# FlipDot_Matrix.net
KiCad netlist of a schematic drawn in Altium Designer
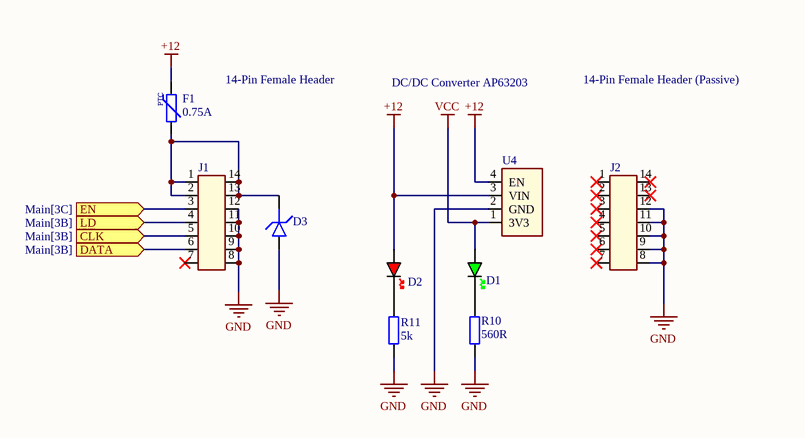
[diagram p0: FlipDot_Matrix.SchDoc]

(export (version "E")
  (design (tool "Eeschema 10.0.6"))
  (components
    (comp (ref "D1")
      (value "GREEN")
      (footprint "LED_0603_GREEN")
      (description "LED 0603 GREEN SMD")
      (libsource (lib "Schematic-Lib-PhilsLab") (part "LED_0603_GREEN"))
    )
    (comp (ref "D2")
      (value "RED")
      (footprint "LED_0603_RED")
      (description "LED 0603 RED SMD")
      (libsource (lib "Schematic-Lib-PhilsLab") (part "LED_0603_RED"))
    )
    (comp (ref "D3")
      (value "D_TVS_0402")
      (footprint "D_0402")
      (description "Diode TVS / ESD 0402")
      (libsource (lib "Schematic-Lib-PhilsLab") (part "D_TVS_0402"))
    )
    (comp (ref "F1")
      (value "0.75A")
      (footprint "FUSE_1206")
      (description "Fuse PPTC SMD 1206")
      (libsource (lib "Schematic-Lib-PhilsLab") (part "FUSE_PPTC_1206"))
    )
    (comp (ref "J1")
      (value "14-Pin Female Header")
      (footprint "PCB_Library_TM:SAMTEC_14_PIN")
      (libsource (lib "Schematic_Library_TM") (part "14-Pin-Connector"))
    )
    (comp (ref "J2")
      (value "14-Pin Female Header (Passive)")
      (footprint "PCB_Library_TM:SAMTEC_14_PIN")
      (libsource (lib "") (part "14-Pin-Connector_1"))
    )
    (comp (ref "R10")
      (value "560R")
      (footprint "RES_0805")
      (description "Resistor SMD 0805")
      (libsource (lib "Schematic-Lib-PhilsLab") (part "RES_0805"))
    )
    (comp (ref "R11")
      (value "5k")
      (footprint "RES_0805")
      (description "Resistor SMD 0805")
      (libsource (lib "Schematic-Lib-PhilsLab") (part "RES_0805"))
    )
    (comp (ref "U4")
      (value "DC/DC Converter AP63203")
      (footprint "DC/DC_CONVERTER")
      (libsource (lib "Schematic_Library_TM") (part "DC/DC Converter AP63203"))
    )
  )
  (nets
    (net (code "1") (name "+12") (class "Default")
      (node (ref "D2") (pin "A") (pinfunction "A_A") (pintype "passive"))
      (node (ref "F1") (pin "2") (pinfunction "2_2") (pintype "passive"))
      (node (ref "U4") (pin "3") (pinfunction "VIN_3") (pintype "power_in"))
      (node (ref "U4") (pin "4") (pinfunction "EN_4") (pintype "power_in"))
    )
    (net (code "2") (name "/CLK") (class "Default")
      (node (ref "J1") (pin "5") (pinfunction "5_5") (pintype "passive"))
    )
    (net (code "3") (name "/DATA") (class "Default")
      (node (ref "J1") (pin "6") (pinfunction "6_6") (pintype "passive"))
    )
    (net (code "4") (name "/EN") (class "Default")
      (node (ref "J1") (pin "3") (pinfunction "3_3") (pintype "passive"))
    )
    (net (code "5") (name "/LD") (class "Default")
      (node (ref "J1") (pin "4") (pinfunction "4_4") (pintype "passive"))
    )
    (net (code "6") (name "GND") (class "Default")
      (node (ref "D3") (pin "A") (pinfunction "A_A") (pintype "passive"))
      (node (ref "J1") (pin "10") (pinfunction "10_10") (pintype "passive"))
      (node (ref "J1") (pin "11") (pinfunction "11_11") (pintype "passive"))
      (node (ref "J1") (pin "12") (pinfunction "12_12") (pintype "passive"))
      (node (ref "J1") (pin "8") (pinfunction "8_8") (pintype "passive"))
      (node (ref "J1") (pin "9") (pinfunction "9_9") (pintype "passive"))
      (node (ref "J2") (pin "10") (pinfunction "10_10") (pintype "passive"))
      (node (ref "J2") (pin "11") (pinfunction "11_11") (pintype "passive"))
      (node (ref "J2") (pin "12") (pinfunction "12_12") (pintype "passive"))
      (node (ref "J2") (pin "8") (pinfunction "8_8") (pintype "passive"))
      (node (ref "J2") (pin "9") (pinfunction "9_9") (pintype "passive"))
      (node (ref "R10") (pin "1") (pinfunction "1_1") (pintype "passive"))
      (node (ref "R11") (pin "1") (pinfunction "1_1") (pintype "passive"))
      (node (ref "U4") (pin "2") (pinfunction "GND_2") (pintype "power_in"))
    )
    (net (code "7") (name "Net-(D1-PadK)") (class "Default")
      (node (ref "D1") (pin "K") (pinfunction "K_K") (pintype "passive"))
      (node (ref "R10") (pin "2") (pinfunction "2_2") (pintype "passive"))
    )
    (net (code "8") (name "Net-(D2-PadK)") (class "Default")
      (node (ref "D2") (pin "K") (pinfunction "K_K") (pintype "passive"))
      (node (ref "R11") (pin "2") (pinfunction "2_2") (pintype "passive"))
    )
    (net (code "9") (name "Net-(D3-PadK)") (class "Default")
      (node (ref "D3") (pin "K") (pinfunction "K_K") (pintype "passive"))
      (node (ref "F1") (pin "1") (pinfunction "1_1") (pintype "passive"))
      (node (ref "J1") (pin "1") (pinfunction "1_1") (pintype "passive"))
      (node (ref "J1") (pin "13") (pinfunction "13_13") (pintype "passive"))
      (node (ref "J1") (pin "14") (pinfunction "14_14") (pintype "passive"))
      (node (ref "J1") (pin "2") (pinfunction "2_2") (pintype "passive"))
    )
    (net (code "10") (name "VCC") (class "Default")
      (node (ref "D1") (pin "A") (pinfunction "A_A") (pintype "passive"))
      (node (ref "U4") (pin "1") (pinfunction "3V3_1") (pintype "power_in"))
    )
    (net (code "11") (name "unconnected-(J1-Pad7)") (class "Default")
      (node (ref "J1") (pin "7") (pinfunction "7_7") (pintype "passive+no_connect"))
    )
    (net (code "12") (name "unconnected-(J2-Pad1)") (class "Default")
      (node (ref "J2") (pin "1") (pinfunction "1_1") (pintype "passive+no_connect"))
    )
    (net (code "13") (name "unconnected-(J2-Pad2)") (class "Default")
      (node (ref "J2") (pin "2") (pinfunction "2_2") (pintype "passive+no_connect"))
    )
    (net (code "14") (name "unconnected-(J2-Pad3)") (class "Default")
      (node (ref "J2") (pin "3") (pinfunction "3_3") (pintype "passive+no_connect"))
    )
    (net (code "15") (name "unconnected-(J2-Pad4)") (class "Default")
      (node (ref "J2") (pin "4") (pinfunction "4_4") (pintype "passive+no_connect"))
    )
    (net (code "16") (name "unconnected-(J2-Pad5)") (class "Default")
      (node (ref "J2") (pin "5") (pinfunction "5_5") (pintype "passive+no_connect"))
    )
    (net (code "17") (name "unconnected-(J2-Pad6)") (class "Default")
      (node (ref "J2") (pin "6") (pinfunction "6_6") (pintype "passive+no_connect"))
    )
    (net (code "18") (name "unconnected-(J2-Pad7)") (class "Default")
      (node (ref "J2") (pin "7") (pinfunction "7_7") (pintype "passive+no_connect"))
    )
    (net (code "19") (name "unconnected-(J2-Pad13)") (class "Default")
      (node (ref "J2") (pin "13") (pinfunction "13_13") (pintype "passive+no_connect"))
    )
    (net (code "20") (name "unconnected-(J2-Pad14)") (class "Default")
      (node (ref "J2") (pin "14") (pinfunction "14_14") (pintype "passive+no_connect"))
    )
  )
)
